# PCB_version_1.net
KiCad netlist of a schematic drawn in EAGLE
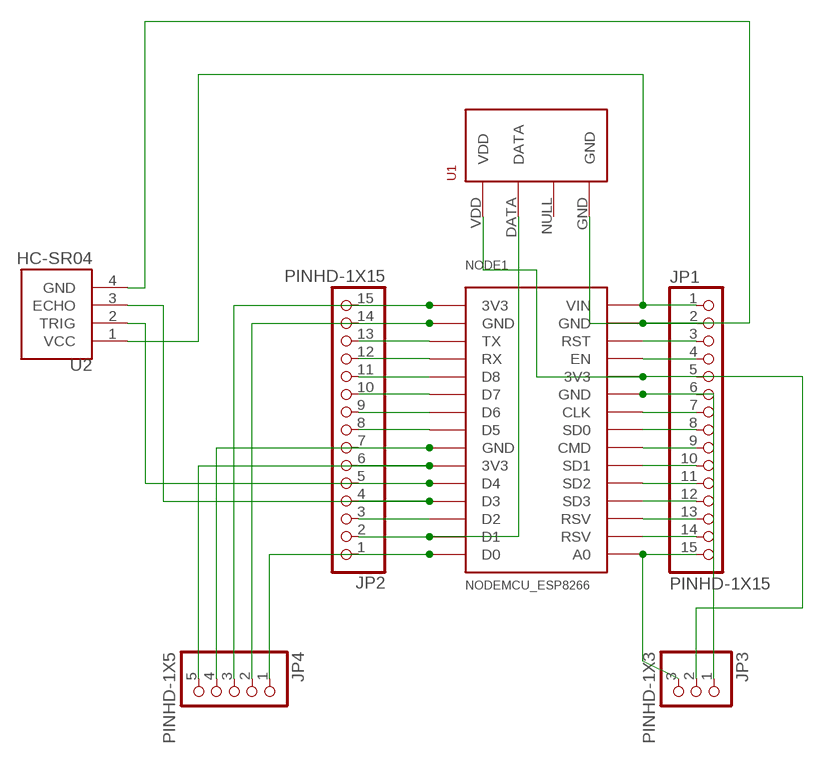
[diagram p0: schematic, sheet 1]

(export (version "E")
  (design (tool "Eeschema 10.0.6"))
  (components
    (comp (ref "JP1")
      (value "PINHD-1X15")
      (footprint "eagle-import:1X15")
      (libsource (lib "eagle-import") (part "PINHD-1X15"))
    )
    (comp (ref "JP2")
      (value "PINHD-1X15")
      (footprint "eagle-import:1X15")
      (libsource (lib "eagle-import") (part "PINHD-1X15"))
    )
    (comp (ref "JP3")
      (value "PINHD-1X3")
      (footprint "eagle-import:1X03")
      (libsource (lib "eagle-import") (part "PINHD-1X3"))
    )
    (comp (ref "JP4")
      (value "PINHD-1X5")
      (footprint "eagle-import:1X05")
      (libsource (lib "eagle-import") (part "PINHD-1X5"))
    )
    (comp (ref "NODE1")
      (value "NODEMCU_ESP8266")
      (footprint "eagle-import:NODEMCU_ESP8266")
      (libsource (lib "eagle-import") (part "NODEMCU_ESP8266"))
    )
    (comp (ref "U1")
      (value "RHT03_DHT-22_AM2302")
      (footprint "eagle-import:RHT03_DHT-22")
      (libsource (lib "eagle-import") (part "RHT03_DHT-22_AM2302"))
    )
    (comp (ref "U2")
      (value "HC-SR04")
      (footprint "eagle-import:XCVR_HC-SR04")
      (fields (field (name "MF") "SparkFun Electronics"))
      (libsource (lib "eagle-import") (part "HC-SR04"))
    )
  )
  (nets
    (net (code "1") (name "Net-(JP1-Pad3)") (class "Default")
      (node (ref "JP1") (pin "3") (pinfunction "3_3") (pintype "passive"))
      (node (ref "NODE1") (pin "RST") (pinfunction "RST_RST") (pintype "bidirectional"))
    )
    (net (code "2") (name "Net-(JP1-Pad4)") (class "Default")
      (node (ref "JP1") (pin "4") (pinfunction "4_4") (pintype "passive"))
      (node (ref "NODE1") (pin "EN") (pinfunction "EN_EN") (pintype "bidirectional"))
    )
    (net (code "3") (name "Net-(JP1-Pad5)") (class "Default")
      (node (ref "JP1") (pin "5") (pinfunction "5_5") (pintype "passive"))
      (node (ref "JP3") (pin "2") (pinfunction "2_2") (pintype "passive"))
      (node (ref "NODE1") (pin "3V3@3") (pinfunction "3V3_3V3@3") (pintype "power_in"))
      (node (ref "U1") (pin "VDD") (pinfunction "VDD_VDD") (pintype "power_in"))
    )
    (net (code "4") (name "Net-(JP1-Pad6)") (class "Default")
      (node (ref "JP1") (pin "6") (pinfunction "6_6") (pintype "passive"))
      (node (ref "JP3") (pin "1") (pinfunction "1_1") (pintype "passive"))
      (node (ref "NODE1") (pin "GND@3") (pinfunction "GND_GND@3") (pintype "power_in"))
    )
    (net (code "5") (name "Net-(JP1-Pad7)") (class "Default")
      (node (ref "JP1") (pin "7") (pinfunction "7_7") (pintype "passive"))
      (node (ref "NODE1") (pin "CLK") (pinfunction "CLK_CLK") (pintype "bidirectional"))
    )
    (net (code "6") (name "Net-(JP1-Pad9)") (class "Default")
      (node (ref "JP1") (pin "9") (pinfunction "9_9") (pintype "passive"))
      (node (ref "NODE1") (pin "CMD") (pinfunction "CMD_CMD") (pintype "bidirectional"))
    )
    (net (code "7") (name "Net-(JP1-Pad10)") (class "Default")
      (node (ref "JP1") (pin "10") (pinfunction "10_10") (pintype "passive"))
      (node (ref "NODE1") (pin "SD1") (pinfunction "SD1_SD1") (pintype "bidirectional"))
    )
    (net (code "8") (name "Net-(JP1-Pad11)") (class "Default")
      (node (ref "JP1") (pin "11") (pinfunction "11_11") (pintype "passive"))
      (node (ref "NODE1") (pin "SD2") (pinfunction "SD2_SD2") (pintype "bidirectional"))
    )
    (net (code "9") (name "Net-(JP1-Pad12)") (class "Default")
      (node (ref "JP1") (pin "12") (pinfunction "12_12") (pintype "passive"))
      (node (ref "NODE1") (pin "SD3") (pinfunction "SD3_SD3") (pintype "bidirectional"))
    )
    (net (code "10") (name "Net-(JP1-Pad13)") (class "Default")
      (node (ref "JP1") (pin "13") (pinfunction "13_13") (pintype "passive"))
      (node (ref "NODE1") (pin "RSV2") (pinfunction "RSV_RSV2") (pintype "bidirectional"))
    )
    (net (code "11") (name "Net-(JP1-Pad14)") (class "Default")
      (node (ref "JP1") (pin "14") (pinfunction "14_14") (pintype "passive"))
      (node (ref "NODE1") (pin "RSV1") (pinfunction "RSV_RSV1") (pintype "bidirectional"))
    )
    (net (code "12") (name "Net-(JP1-Pad15)") (class "Default")
      (node (ref "JP1") (pin "15") (pinfunction "15_15") (pintype "passive"))
      (node (ref "JP3") (pin "3") (pinfunction "3_3") (pintype "passive"))
      (node (ref "NODE1") (pin "A0") (pinfunction "A0_A0") (pintype "bidirectional"))
    )
    (net (code "13") (name "Net-(JP2-Pad1)") (class "Default")
      (node (ref "JP2") (pin "1") (pinfunction "1_1") (pintype "passive"))
      (node (ref "JP4") (pin "1") (pinfunction "1_1") (pintype "passive"))
      (node (ref "NODE1") (pin "D0") (pinfunction "D0_D0") (pintype "bidirectional"))
    )
    (net (code "14") (name "Net-(JP2-Pad2)") (class "Default")
      (node (ref "JP2") (pin "2") (pinfunction "2_2") (pintype "passive"))
      (node (ref "NODE1") (pin "D1") (pinfunction "D1_D1") (pintype "bidirectional"))
      (node (ref "U1") (pin "DATA") (pinfunction "DATA_DATA") (pintype "bidirectional"))
    )
    (net (code "15") (name "Net-(JP2-Pad3)") (class "Default")
      (node (ref "JP2") (pin "3") (pinfunction "3_3") (pintype "passive"))
      (node (ref "NODE1") (pin "D2") (pinfunction "D2_D2") (pintype "bidirectional"))
    )
    (net (code "16") (name "Net-(JP2-Pad6)") (class "Default")
      (node (ref "JP2") (pin "6") (pinfunction "6_6") (pintype "passive"))
      (node (ref "JP4") (pin "5") (pinfunction "5_5") (pintype "passive"))
      (node (ref "NODE1") (pin "3V3@2") (pinfunction "3V3_3V3@2") (pintype "power_in"))
    )
    (net (code "17") (name "Net-(JP2-Pad7)") (class "Default")
      (node (ref "JP2") (pin "7") (pinfunction "7_7") (pintype "passive"))
      (node (ref "JP4") (pin "4") (pinfunction "4_4") (pintype "passive"))
      (node (ref "NODE1") (pin "GND@2") (pinfunction "GND_GND@2") (pintype "power_in"))
    )
    (net (code "18") (name "Net-(JP2-Pad8)") (class "Default")
      (node (ref "JP2") (pin "8") (pinfunction "8_8") (pintype "passive"))
      (node (ref "NODE1") (pin "D5") (pinfunction "D5_D5") (pintype "bidirectional"))
    )
    (net (code "19") (name "Net-(JP2-Pad9)") (class "Default")
      (node (ref "JP2") (pin "9") (pinfunction "9_9") (pintype "passive"))
      (node (ref "NODE1") (pin "D6") (pinfunction "D6_D6") (pintype "bidirectional"))
    )
    (net (code "20") (name "Net-(JP2-Pad10)") (class "Default")
      (node (ref "JP2") (pin "10") (pinfunction "10_10") (pintype "passive"))
      (node (ref "NODE1") (pin "D7") (pinfunction "D7_D7") (pintype "bidirectional"))
    )
    (net (code "21") (name "Net-(JP2-Pad11)") (class "Default")
      (node (ref "JP2") (pin "11") (pinfunction "11_11") (pintype "passive"))
      (node (ref "NODE1") (pin "D8") (pinfunction "D8_D8") (pintype "bidirectional"))
    )
    (net (code "22") (name "Net-(JP2-Pad12)") (class "Default")
      (node (ref "JP2") (pin "12") (pinfunction "12_12") (pintype "passive"))
      (node (ref "NODE1") (pin "RX") (pinfunction "RX_RX") (pintype "bidirectional"))
    )
    (net (code "23") (name "Net-(JP2-Pad13)") (class "Default")
      (node (ref "JP2") (pin "13") (pinfunction "13_13") (pintype "passive"))
      (node (ref "NODE1") (pin "TX") (pinfunction "TX_TX") (pintype "bidirectional"))
    )
    (net (code "24") (name "Net-(JP2-Pad14)") (class "Default")
      (node (ref "JP2") (pin "14") (pinfunction "14_14") (pintype "passive"))
      (node (ref "JP4") (pin "2") (pinfunction "2_2") (pintype "passive"))
      (node (ref "NODE1") (pin "GND@1") (pinfunction "GND_GND@1") (pintype "power_in"))
    )
    (net (code "25") (name "Net-(JP2-Pad15)") (class "Default")
      (node (ref "JP2") (pin "15") (pinfunction "15_15") (pintype "passive"))
      (node (ref "JP4") (pin "3") (pinfunction "3_3") (pintype "passive"))
      (node (ref "NODE1") (pin "3V3@1") (pinfunction "3V3_3V3@1") (pintype "power_in"))
    )
    (net (code "26") (name "Net-(NODE1-SD0)") (class "Default")
      (node (ref "JP1") (pin "8") (pinfunction "8_8") (pintype "passive"))
      (node (ref "NODE1") (pin "SDO") (pinfunction "SD0_SDO") (pintype "bidirectional"))
    )
    (net (code "27") (name "Net-(U2-ECHO)") (class "Default")
      (node (ref "JP2") (pin "4") (pinfunction "4_4") (pintype "passive"))
      (node (ref "NODE1") (pin "D3") (pinfunction "D3_D3") (pintype "bidirectional"))
      (node (ref "U2") (pin "3") (pinfunction "ECHO_3") (pintype "bidirectional"))
    )
    (net (code "28") (name "Net-(U2-GND)") (class "Default")
      (node (ref "JP1") (pin "2") (pinfunction "2_2") (pintype "passive"))
      (node (ref "NODE1") (pin "GND@4") (pinfunction "GND_GND@4") (pintype "power_in"))
      (node (ref "U1") (pin "GND") (pinfunction "GND_GND") (pintype "power_in"))
      (node (ref "U2") (pin "4") (pinfunction "GND_4") (pintype "power_in"))
    )
    (net (code "29") (name "Net-(U2-TRIG)") (class "Default")
      (node (ref "JP2") (pin "5") (pinfunction "5_5") (pintype "passive"))
      (node (ref "NODE1") (pin "D4") (pinfunction "D4_D4") (pintype "bidirectional"))
      (node (ref "U2") (pin "2") (pinfunction "TRIG_2") (pintype "bidirectional"))
    )
    (net (code "30") (name "Net-(U2-VCC)") (class "Default")
      (node (ref "JP1") (pin "1") (pinfunction "1_1") (pintype "passive"))
      (node (ref "NODE1") (pin "VIN") (pinfunction "VIN_VIN") (pintype "power_in"))
      (node (ref "U2") (pin "1") (pinfunction "VCC_1") (pintype "power_in"))
    )
    (net (code "31") (name "unconnected-(U1-PadNULL)") (class "Default")
      (node (ref "U1") (pin "NULL") (pinfunction "NULL_NULL") (pintype "no_connect"))
    )
  )
)
